# micro-sd-wing.net
KiCad netlist of a schematic drawn in Altium Designer
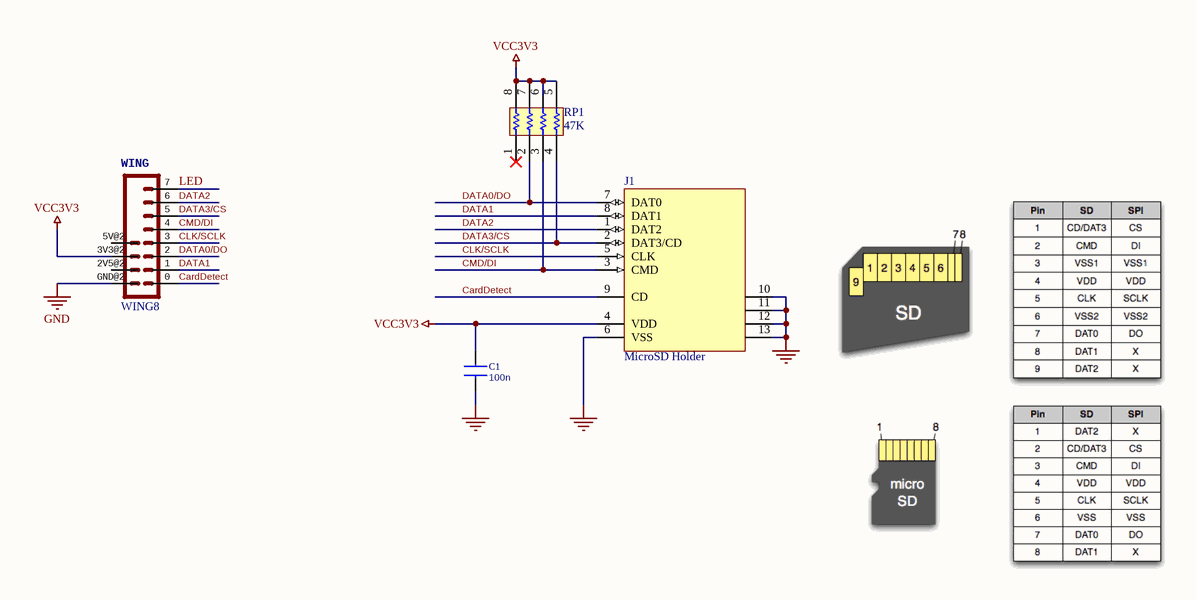
[diagram p0: micro-sd-wing.SchDoc]

(export (version "E")
  (design (tool "Eeschema 10.0.6"))
  (components
    (comp (ref "C1")
      (value "100n")
      (footprint "C0805_M")
      (description "Ceramic Capactor size 0805")
      (libsource (lib "MH - RCLDSX") (part "C0805"))
    )
    (comp (ref "J1")
      (value "MicroSD Holder")
      (footprint "micro sd soket")
      (description "MicroSD Memory Card Holder")
      (libsource (lib "MH - Connectors") (part "MicroSD"))
    )
    (comp (ref "RP1")
      (value "47K")
      (footprint "RESCAXS50P160X320X70-8N")
      (description "Isolated Resistor Network")
      (libsource (lib "MH - RCLDSX") (part "RESPACK_4X"))
    )
    (comp (ref "WING") (value "WING8") (footprint "WINGSIDE_8BIT") (libsource (lib "Papilio") (part "WING8")))
  )
  (nets
    (net (code "1") (name "/CLK{slash}SCLK") (class "Default")
      (node (ref "J1") (pin "5") (pinfunction "CLK_5") (pintype "input"))
      (node (ref "WING") (pin "3") (pinfunction "4_3") (pintype "passive"))
    )
    (net (code "2") (name "/CMD{slash}DI") (class "Default")
      (node (ref "J1") (pin "3") (pinfunction "CMD_3") (pintype "input"))
      (node (ref "RP1") (pin "3") (pintype "passive"))
      (node (ref "WING") (pin "4") (pinfunction "5_4") (pintype "passive"))
    )
    (net (code "3") (name "/CardDetect") (class "Default")
      (node (ref "J1") (pin "9") (pinfunction "CD_9") (pintype "passive"))
      (node (ref "WING") (pin "0") (pinfunction "1_0") (pintype "passive"))
    )
    (net (code "4") (name "/DATA0{slash}DO") (class "Default")
      (node (ref "J1") (pin "7") (pinfunction "DAT0_7") (pintype "bidirectional"))
      (node (ref "RP1") (pin "2") (pintype "passive"))
      (node (ref "WING") (pin "2") (pinfunction "3_2") (pintype "passive"))
    )
    (net (code "5") (name "/DATA1") (class "Default")
      (node (ref "J1") (pin "8") (pinfunction "DAT1_8") (pintype "bidirectional"))
      (node (ref "WING") (pin "1") (pinfunction "2_1") (pintype "passive"))
    )
    (net (code "6") (name "/DATA2") (class "Default")
      (node (ref "J1") (pin "1") (pinfunction "DAT2_1") (pintype "bidirectional"))
      (node (ref "WING") (pin "6") (pinfunction "7_6") (pintype "passive"))
    )
    (net (code "7") (name "/DATA3{slash}CS") (class "Default")
      (node (ref "J1") (pin "2") (pinfunction "DAT3/CD_2") (pintype "bidirectional"))
      (node (ref "RP1") (pin "4") (pintype "passive"))
      (node (ref "WING") (pin "5") (pinfunction "6_5") (pintype "passive"))
    )
    (net (code "8") (name "/LED") (class "Default")
      (node (ref "WING") (pin "7") (pinfunction "8_7") (pintype "passive"))
    )
    (net (code "9") (name "GND") (class "Default")
      (node (ref "C1") (pin "1") (pintype "passive"))
      (node (ref "J1") (pin "10") (pintype "passive"))
      (node (ref "J1") (pin "11") (pintype "passive"))
      (node (ref "J1") (pin "12") (pintype "passive"))
      (node (ref "J1") (pin "13") (pintype "passive"))
      (node (ref "J1") (pin "6") (pinfunction "VSS_6") (pintype "power_in"))
      (node (ref "WING") (pin "GND@2") (pinfunction "GND_GND@2") (pintype "passive"))
    )
    (net (code "10") (name "VCC3V3") (class "Default")
      (node (ref "C1") (pin "2") (pintype "passive"))
      (node (ref "J1") (pin "4") (pinfunction "VDD_4") (pintype "power_in"))
      (node (ref "RP1") (pin "5") (pintype "passive"))
      (node (ref "RP1") (pin "6") (pintype "passive"))
      (node (ref "RP1") (pin "7") (pintype "passive"))
      (node (ref "RP1") (pin "8") (pintype "passive"))
      (node (ref "WING") (pin "3V3@2") (pinfunction "3V3_3V3@2") (pintype "passive"))
    )
    (net (code "11") (name "unconnected-(RP1-Pad1)") (class "Default")
      (node (ref "RP1") (pin "1") (pintype "passive+no_connect"))
    )
    (net (code "12") (name "unconnected-(WING-2V5-Pad2V5@2)") (class "Default")
      (node (ref "WING") (pin "2V5@2") (pinfunction "2V5_2V5@2") (pintype "passive"))
    )
    (net (code "13") (name "unconnected-(WING-5V-Pad5V@2)") (class "Default")
      (node (ref "WING") (pin "5V@2") (pinfunction "5V_5V@2") (pintype "passive"))
    )
  )
)
